# matchbox_bob_v11.net
KiCad netlist of a schematic drawn in EAGLE
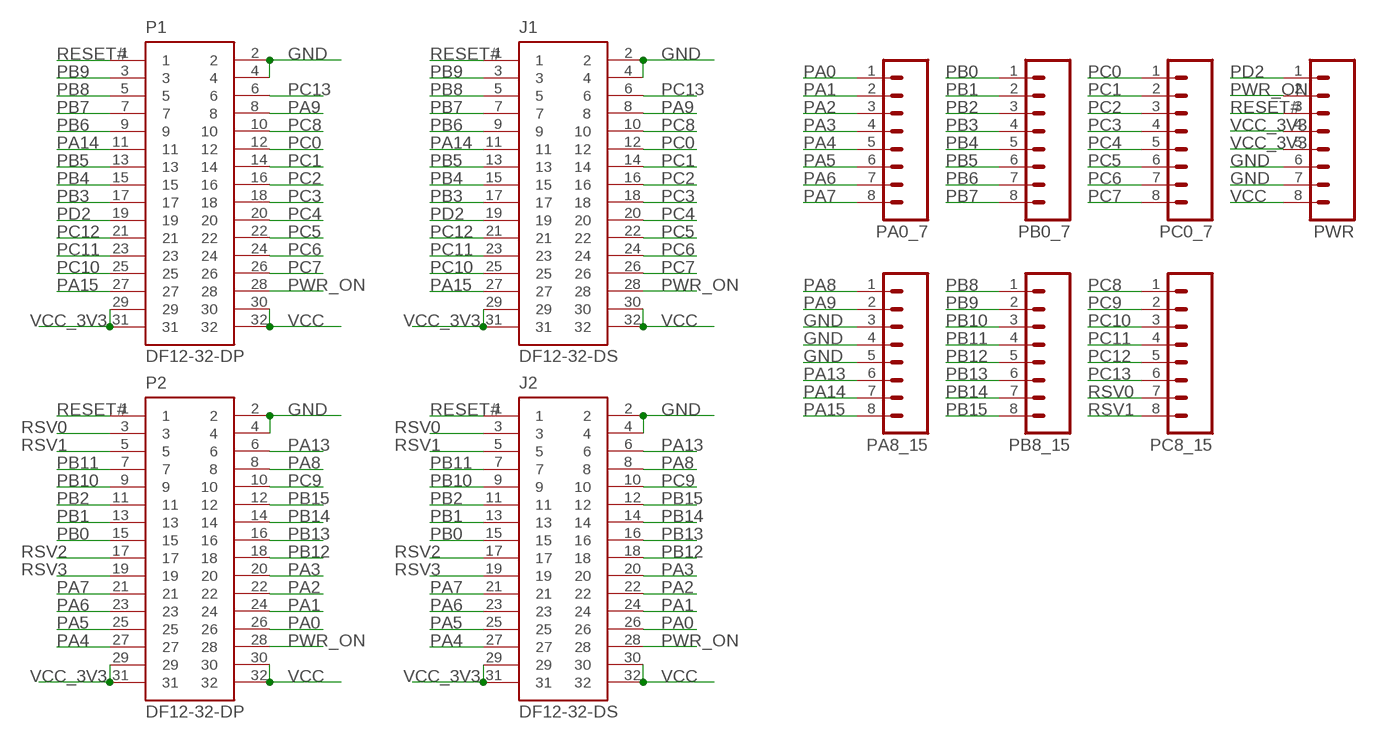
[diagram p0: schematic, sheet 1]

(export (version "E")
  (design (tool "Eeschema 10.0.6"))
  (components
    (comp (ref "J1")
      (value "DF12-32-DS")
      (footprint "eagle-import:DF12-32-DS")
      (fields (field (name "PARTNO") "AS-ITM-00012"))
      (libsource (lib "eagle-import") (part "AS-ITM-00012"))
    )
    (comp (ref "J2")
      (value "DF12-32-DS")
      (footprint "eagle-import:DF12-32-DS")
      (fields (field (name "PARTNO") "AS-ITM-00012"))
      (libsource (lib "eagle-import") (part "AS-ITM-00012"))
    )
    (comp (ref "P1")
      (value "DF12-32-DP")
      (footprint "eagle-import:DF12-32-DP")
      (fields (field (name "PARTNO") "AS-ITM-00015"))
      (libsource (lib "eagle-import") (part "AS-ITM-00015"))
    )
    (comp (ref "P2")
      (value "DF12-32-DP")
      (footprint "eagle-import:DF12-32-DP")
      (fields (field (name "PARTNO") "AS-ITM-00015"))
      (libsource (lib "eagle-import") (part "AS-ITM-00015"))
    )
    (comp (ref "PA0_7")
      (value "M08FEMALE_LOCK")
      (footprint "eagle-import:1X08_FEMALE_LOCK")
      (libsource (lib "eagle-import") (part "M08FEMALE_LOCK"))
    )
    (comp (ref "PA8_15")
      (value "M08FEMALE_LOCK")
      (footprint "eagle-import:1X08_FEMALE_LOCK")
      (libsource (lib "eagle-import") (part "M08FEMALE_LOCK"))
    )
    (comp (ref "PB0_7")
      (value "M08FEMALE_LOCK")
      (footprint "eagle-import:1X08_FEMALE_LOCK")
      (libsource (lib "eagle-import") (part "M08FEMALE_LOCK"))
    )
    (comp (ref "PB8_15")
      (value "M08FEMALE_LOCK")
      (footprint "eagle-import:1X08_FEMALE_LOCK")
      (libsource (lib "eagle-import") (part "M08FEMALE_LOCK"))
    )
    (comp (ref "PC0_7")
      (value "M08FEMALE_LOCK")
      (footprint "eagle-import:1X08_FEMALE_LOCK")
      (libsource (lib "eagle-import") (part "M08FEMALE_LOCK"))
    )
    (comp (ref "PC8_15")
      (value "M08FEMALE_LOCK")
      (footprint "eagle-import:1X08_FEMALE_LOCK")
      (libsource (lib "eagle-import") (part "M08FEMALE_LOCK"))
    )
    (comp (ref "PWR")
      (value "M08FEMALE_LOCK")
      (footprint "eagle-import:1X08_FEMALE_LOCK")
      (libsource (lib "eagle-import") (part "M08FEMALE_LOCK"))
    )
  )
  (nets
    (net (code "1") (name "/GND") (class "Default")
      (node (ref "J1") (pin "2") (pinfunction "2_2") (pintype "bidirectional"))
      (node (ref "J1") (pin "4") (pinfunction "4_4") (pintype "bidirectional"))
      (node (ref "J2") (pin "2") (pinfunction "2_2") (pintype "bidirectional"))
      (node (ref "J2") (pin "4") (pinfunction "4_4") (pintype "bidirectional"))
      (node (ref "P1") (pin "2") (pinfunction "2_2") (pintype "bidirectional"))
      (node (ref "P1") (pin "4") (pinfunction "4_4") (pintype "bidirectional"))
      (node (ref "P2") (pin "2") (pinfunction "2_2") (pintype "bidirectional"))
      (node (ref "P2") (pin "4") (pinfunction "4_4") (pintype "bidirectional"))
      (node (ref "PA8_15") (pin "3") (pinfunction "3_3") (pintype "passive"))
      (node (ref "PA8_15") (pin "4") (pinfunction "4_4") (pintype "passive"))
      (node (ref "PA8_15") (pin "5") (pinfunction "5_5") (pintype "passive"))
      (node (ref "PWR") (pin "6") (pinfunction "6_6") (pintype "passive"))
      (node (ref "PWR") (pin "7") (pinfunction "7_7") (pintype "passive"))
    )
    (net (code "2") (name "/PA0") (class "Default")
      (node (ref "J2") (pin "26") (pinfunction "26_26") (pintype "bidirectional"))
      (node (ref "P2") (pin "26") (pinfunction "26_26") (pintype "bidirectional"))
      (node (ref "PA0_7") (pin "1") (pinfunction "1_1") (pintype "passive"))
    )
    (net (code "3") (name "/PA1") (class "Default")
      (node (ref "J2") (pin "24") (pinfunction "24_24") (pintype "bidirectional"))
      (node (ref "P2") (pin "24") (pinfunction "24_24") (pintype "bidirectional"))
      (node (ref "PA0_7") (pin "2") (pinfunction "2_2") (pintype "passive"))
    )
    (net (code "4") (name "/PA2") (class "Default")
      (node (ref "J2") (pin "22") (pinfunction "22_22") (pintype "bidirectional"))
      (node (ref "P2") (pin "22") (pinfunction "22_22") (pintype "bidirectional"))
      (node (ref "PA0_7") (pin "3") (pinfunction "3_3") (pintype "passive"))
    )
    (net (code "5") (name "/PA3") (class "Default")
      (node (ref "J2") (pin "20") (pinfunction "20_20") (pintype "bidirectional"))
      (node (ref "P2") (pin "20") (pinfunction "20_20") (pintype "bidirectional"))
      (node (ref "PA0_7") (pin "4") (pinfunction "4_4") (pintype "passive"))
    )
    (net (code "6") (name "/PA4") (class "Default")
      (node (ref "J2") (pin "27") (pinfunction "27_27") (pintype "bidirectional"))
      (node (ref "P2") (pin "27") (pinfunction "27_27") (pintype "bidirectional"))
      (node (ref "PA0_7") (pin "5") (pinfunction "5_5") (pintype "passive"))
    )
    (net (code "7") (name "/PA5") (class "Default")
      (node (ref "J2") (pin "25") (pinfunction "25_25") (pintype "bidirectional"))
      (node (ref "P2") (pin "25") (pinfunction "25_25") (pintype "bidirectional"))
      (node (ref "PA0_7") (pin "6") (pinfunction "6_6") (pintype "passive"))
    )
    (net (code "8") (name "/PA6") (class "Default")
      (node (ref "J2") (pin "23") (pinfunction "23_23") (pintype "bidirectional"))
      (node (ref "P2") (pin "23") (pinfunction "23_23") (pintype "bidirectional"))
      (node (ref "PA0_7") (pin "7") (pinfunction "7_7") (pintype "passive"))
    )
    (net (code "9") (name "/PA7") (class "Default")
      (node (ref "J2") (pin "21") (pinfunction "21_21") (pintype "bidirectional"))
      (node (ref "P2") (pin "21") (pinfunction "21_21") (pintype "bidirectional"))
      (node (ref "PA0_7") (pin "8") (pinfunction "8_8") (pintype "passive"))
    )
    (net (code "10") (name "/PA8") (class "Default")
      (node (ref "J2") (pin "8") (pinfunction "8_8") (pintype "bidirectional"))
      (node (ref "P2") (pin "8") (pinfunction "8_8") (pintype "bidirectional"))
      (node (ref "PA8_15") (pin "1") (pinfunction "1_1") (pintype "passive"))
    )
    (net (code "11") (name "/PA9") (class "Default")
      (node (ref "J1") (pin "8") (pinfunction "8_8") (pintype "bidirectional"))
      (node (ref "P1") (pin "8") (pinfunction "8_8") (pintype "bidirectional"))
      (node (ref "PA8_15") (pin "2") (pinfunction "2_2") (pintype "passive"))
    )
    (net (code "12") (name "/PA13") (class "Default")
      (node (ref "J2") (pin "6") (pinfunction "6_6") (pintype "bidirectional"))
      (node (ref "P2") (pin "6") (pinfunction "6_6") (pintype "bidirectional"))
      (node (ref "PA8_15") (pin "6") (pinfunction "6_6") (pintype "passive"))
    )
    (net (code "13") (name "/PA14") (class "Default")
      (node (ref "J1") (pin "11") (pinfunction "11_11") (pintype "bidirectional"))
      (node (ref "P1") (pin "11") (pinfunction "11_11") (pintype "bidirectional"))
      (node (ref "PA8_15") (pin "7") (pinfunction "7_7") (pintype "passive"))
    )
    (net (code "14") (name "/PA15") (class "Default")
      (node (ref "J1") (pin "27") (pinfunction "27_27") (pintype "bidirectional"))
      (node (ref "P1") (pin "27") (pinfunction "27_27") (pintype "bidirectional"))
      (node (ref "PA8_15") (pin "8") (pinfunction "8_8") (pintype "passive"))
    )
    (net (code "15") (name "/PB0") (class "Default")
      (node (ref "J2") (pin "15") (pinfunction "15_15") (pintype "bidirectional"))
      (node (ref "P2") (pin "15") (pinfunction "15_15") (pintype "bidirectional"))
      (node (ref "PB0_7") (pin "1") (pinfunction "1_1") (pintype "passive"))
    )
    (net (code "16") (name "/PB1") (class "Default")
      (node (ref "J2") (pin "13") (pinfunction "13_13") (pintype "bidirectional"))
      (node (ref "P2") (pin "13") (pinfunction "13_13") (pintype "bidirectional"))
      (node (ref "PB0_7") (pin "2") (pinfunction "2_2") (pintype "passive"))
    )
    (net (code "17") (name "/PB2") (class "Default")
      (node (ref "J2") (pin "11") (pinfunction "11_11") (pintype "bidirectional"))
      (node (ref "P2") (pin "11") (pinfunction "11_11") (pintype "bidirectional"))
      (node (ref "PB0_7") (pin "3") (pinfunction "3_3") (pintype "passive"))
    )
    (net (code "18") (name "/PB3") (class "Default")
      (node (ref "J1") (pin "17") (pinfunction "17_17") (pintype "bidirectional"))
      (node (ref "P1") (pin "17") (pinfunction "17_17") (pintype "bidirectional"))
      (node (ref "PB0_7") (pin "4") (pinfunction "4_4") (pintype "passive"))
    )
    (net (code "19") (name "/PB4") (class "Default")
      (node (ref "J1") (pin "15") (pinfunction "15_15") (pintype "bidirectional"))
      (node (ref "P1") (pin "15") (pinfunction "15_15") (pintype "bidirectional"))
      (node (ref "PB0_7") (pin "5") (pinfunction "5_5") (pintype "passive"))
    )
    (net (code "20") (name "/PB5") (class "Default")
      (node (ref "J1") (pin "13") (pinfunction "13_13") (pintype "bidirectional"))
      (node (ref "P1") (pin "13") (pinfunction "13_13") (pintype "bidirectional"))
      (node (ref "PB0_7") (pin "6") (pinfunction "6_6") (pintype "passive"))
    )
    (net (code "21") (name "/PB6") (class "Default")
      (node (ref "J1") (pin "9") (pinfunction "9_9") (pintype "bidirectional"))
      (node (ref "P1") (pin "9") (pinfunction "9_9") (pintype "bidirectional"))
      (node (ref "PB0_7") (pin "7") (pinfunction "7_7") (pintype "passive"))
    )
    (net (code "22") (name "/PB7") (class "Default")
      (node (ref "J1") (pin "7") (pinfunction "7_7") (pintype "bidirectional"))
      (node (ref "P1") (pin "7") (pinfunction "7_7") (pintype "bidirectional"))
      (node (ref "PB0_7") (pin "8") (pinfunction "8_8") (pintype "passive"))
    )
    (net (code "23") (name "/PB8") (class "Default")
      (node (ref "J1") (pin "5") (pinfunction "5_5") (pintype "bidirectional"))
      (node (ref "P1") (pin "5") (pinfunction "5_5") (pintype "bidirectional"))
      (node (ref "PB8_15") (pin "1") (pinfunction "1_1") (pintype "passive"))
    )
    (net (code "24") (name "/PB9") (class "Default")
      (node (ref "J1") (pin "3") (pinfunction "3_3") (pintype "bidirectional"))
      (node (ref "P1") (pin "3") (pinfunction "3_3") (pintype "bidirectional"))
      (node (ref "PB8_15") (pin "2") (pinfunction "2_2") (pintype "passive"))
    )
    (net (code "25") (name "/PB10") (class "Default")
      (node (ref "J2") (pin "9") (pinfunction "9_9") (pintype "bidirectional"))
      (node (ref "P2") (pin "9") (pinfunction "9_9") (pintype "bidirectional"))
      (node (ref "PB8_15") (pin "3") (pinfunction "3_3") (pintype "passive"))
    )
    (net (code "26") (name "/PB11") (class "Default")
      (node (ref "J2") (pin "7") (pinfunction "7_7") (pintype "bidirectional"))
      (node (ref "P2") (pin "7") (pinfunction "7_7") (pintype "bidirectional"))
      (node (ref "PB8_15") (pin "4") (pinfunction "4_4") (pintype "passive"))
    )
    (net (code "27") (name "/PB12") (class "Default")
      (node (ref "J2") (pin "18") (pinfunction "18_18") (pintype "bidirectional"))
      (node (ref "P2") (pin "18") (pinfunction "18_18") (pintype "bidirectional"))
      (node (ref "PB8_15") (pin "5") (pinfunction "5_5") (pintype "passive"))
    )
    (net (code "28") (name "/PB13") (class "Default")
      (node (ref "J2") (pin "16") (pinfunction "16_16") (pintype "bidirectional"))
      (node (ref "P2") (pin "16") (pinfunction "16_16") (pintype "bidirectional"))
      (node (ref "PB8_15") (pin "6") (pinfunction "6_6") (pintype "passive"))
    )
    (net (code "29") (name "/PB14") (class "Default")
      (node (ref "J2") (pin "14") (pinfunction "14_14") (pintype "bidirectional"))
      (node (ref "P2") (pin "14") (pinfunction "14_14") (pintype "bidirectional"))
      (node (ref "PB8_15") (pin "7") (pinfunction "7_7") (pintype "passive"))
    )
    (net (code "30") (name "/PB15") (class "Default")
      (node (ref "J2") (pin "12") (pinfunction "12_12") (pintype "bidirectional"))
      (node (ref "P2") (pin "12") (pinfunction "12_12") (pintype "bidirectional"))
      (node (ref "PB8_15") (pin "8") (pinfunction "8_8") (pintype "passive"))
    )
    (net (code "31") (name "/PC0") (class "Default")
      (node (ref "J1") (pin "12") (pinfunction "12_12") (pintype "bidirectional"))
      (node (ref "P1") (pin "12") (pinfunction "12_12") (pintype "bidirectional"))
      (node (ref "PC0_7") (pin "1") (pinfunction "1_1") (pintype "passive"))
    )
    (net (code "32") (name "/PC1") (class "Default")
      (node (ref "J1") (pin "14") (pinfunction "14_14") (pintype "bidirectional"))
      (node (ref "P1") (pin "14") (pinfunction "14_14") (pintype "bidirectional"))
      (node (ref "PC0_7") (pin "2") (pinfunction "2_2") (pintype "passive"))
    )
    (net (code "33") (name "/PC2") (class "Default")
      (node (ref "J1") (pin "16") (pinfunction "16_16") (pintype "bidirectional"))
      (node (ref "P1") (pin "16") (pinfunction "16_16") (pintype "bidirectional"))
      (node (ref "PC0_7") (pin "3") (pinfunction "3_3") (pintype "passive"))
    )
    (net (code "34") (name "/PC3") (class "Default")
      (node (ref "J1") (pin "18") (pinfunction "18_18") (pintype "bidirectional"))
      (node (ref "P1") (pin "18") (pinfunction "18_18") (pintype "bidirectional"))
      (node (ref "PC0_7") (pin "4") (pinfunction "4_4") (pintype "passive"))
    )
    (net (code "35") (name "/PC4") (class "Default")
      (node (ref "J1") (pin "20") (pinfunction "20_20") (pintype "bidirectional"))
      (node (ref "P1") (pin "20") (pinfunction "20_20") (pintype "bidirectional"))
      (node (ref "PC0_7") (pin "5") (pinfunction "5_5") (pintype "passive"))
    )
    (net (code "36") (name "/PC5") (class "Default")
      (node (ref "J1") (pin "22") (pinfunction "22_22") (pintype "bidirectional"))
      (node (ref "P1") (pin "22") (pinfunction "22_22") (pintype "bidirectional"))
      (node (ref "PC0_7") (pin "6") (pinfunction "6_6") (pintype "passive"))
    )
    (net (code "37") (name "/PC6") (class "Default")
      (node (ref "J1") (pin "24") (pinfunction "24_24") (pintype "bidirectional"))
      (node (ref "P1") (pin "24") (pinfunction "24_24") (pintype "bidirectional"))
      (node (ref "PC0_7") (pin "7") (pinfunction "7_7") (pintype "passive"))
    )
    (net (code "38") (name "/PC7") (class "Default")
      (node (ref "J1") (pin "26") (pinfunction "26_26") (pintype "bidirectional"))
      (node (ref "P1") (pin "26") (pinfunction "26_26") (pintype "bidirectional"))
      (node (ref "PC0_7") (pin "8") (pinfunction "8_8") (pintype "passive"))
    )
    (net (code "39") (name "/PC8") (class "Default")
      (node (ref "J1") (pin "10") (pinfunction "10_10") (pintype "bidirectional"))
      (node (ref "P1") (pin "10") (pinfunction "10_10") (pintype "bidirectional"))
      (node (ref "PC8_15") (pin "1") (pinfunction "1_1") (pintype "passive"))
    )
    (net (code "40") (name "/PC9") (class "Default")
      (node (ref "J2") (pin "10") (pinfunction "10_10") (pintype "bidirectional"))
      (node (ref "P2") (pin "10") (pinfunction "10_10") (pintype "bidirectional"))
      (node (ref "PC8_15") (pin "2") (pinfunction "2_2") (pintype "passive"))
    )
    (net (code "41") (name "/PC10") (class "Default")
      (node (ref "J1") (pin "25") (pinfunction "25_25") (pintype "bidirectional"))
      (node (ref "P1") (pin "25") (pinfunction "25_25") (pintype "bidirectional"))
      (node (ref "PC8_15") (pin "3") (pinfunction "3_3") (pintype "passive"))
    )
    (net (code "42") (name "/PC11") (class "Default")
      (node (ref "J1") (pin "23") (pinfunction "23_23") (pintype "bidirectional"))
      (node (ref "P1") (pin "23") (pinfunction "23_23") (pintype "bidirectional"))
      (node (ref "PC8_15") (pin "4") (pinfunction "4_4") (pintype "passive"))
    )
    (net (code "43") (name "/PC12") (class "Default")
      (node (ref "J1") (pin "21") (pinfunction "21_21") (pintype "bidirectional"))
      (node (ref "P1") (pin "21") (pinfunction "21_21") (pintype "bidirectional"))
      (node (ref "PC8_15") (pin "5") (pinfunction "5_5") (pintype "passive"))
    )
    (net (code "44") (name "/PC13") (class "Default")
      (node (ref "J1") (pin "6") (pinfunction "6_6") (pintype "bidirectional"))
      (node (ref "P1") (pin "6") (pinfunction "6_6") (pintype "bidirectional"))
      (node (ref "PC8_15") (pin "6") (pinfunction "6_6") (pintype "passive"))
    )
    (net (code "45") (name "/PD2") (class "Default")
      (node (ref "J1") (pin "19") (pinfunction "19_19") (pintype "bidirectional"))
      (node (ref "P1") (pin "19") (pinfunction "19_19") (pintype "bidirectional"))
      (node (ref "PWR") (pin "1") (pinfunction "1_1") (pintype "passive"))
    )
    (net (code "46") (name "/PWR_ON") (class "Default")
      (node (ref "J1") (pin "28") (pinfunction "28_28") (pintype "bidirectional"))
      (node (ref "J2") (pin "28") (pinfunction "28_28") (pintype "bidirectional"))
      (node (ref "P1") (pin "28") (pinfunction "28_28") (pintype "bidirectional"))
      (node (ref "P2") (pin "28") (pinfunction "28_28") (pintype "bidirectional"))
      (node (ref "PWR") (pin "2") (pinfunction "2_2") (pintype "passive"))
    )
    (net (code "47") (name "/RESET#") (class "Default")
      (node (ref "J1") (pin "1") (pinfunction "1_1") (pintype "bidirectional"))
      (node (ref "J2") (pin "1") (pinfunction "1_1") (pintype "bidirectional"))
      (node (ref "P1") (pin "1") (pinfunction "1_1") (pintype "bidirectional"))
      (node (ref "P2") (pin "1") (pinfunction "1_1") (pintype "bidirectional"))
      (node (ref "PWR") (pin "3") (pinfunction "3_3") (pintype "passive"))
    )
    (net (code "48") (name "/RSV0") (class "Default")
      (node (ref "J2") (pin "3") (pinfunction "3_3") (pintype "bidirectional"))
      (node (ref "P2") (pin "3") (pinfunction "3_3") (pintype "bidirectional"))
      (node (ref "PC8_15") (pin "7") (pinfunction "7_7") (pintype "passive"))
    )
    (net (code "49") (name "/RSV1") (class "Default")
      (node (ref "J2") (pin "5") (pinfunction "5_5") (pintype "bidirectional"))
      (node (ref "P2") (pin "5") (pinfunction "5_5") (pintype "bidirectional"))
      (node (ref "PC8_15") (pin "8") (pinfunction "8_8") (pintype "passive"))
    )
    (net (code "50") (name "/RSV2") (class "Default")
      (node (ref "J2") (pin "17") (pinfunction "17_17") (pintype "bidirectional"))
      (node (ref "P2") (pin "17") (pinfunction "17_17") (pintype "bidirectional"))
    )
    (net (code "51") (name "/RSV3") (class "Default")
      (node (ref "J2") (pin "19") (pinfunction "19_19") (pintype "bidirectional"))
      (node (ref "P2") (pin "19") (pinfunction "19_19") (pintype "bidirectional"))
    )
    (net (code "52") (name "/VCC") (class "Default")
      (node (ref "J1") (pin "30") (pinfunction "30_30") (pintype "bidirectional"))
      (node (ref "J1") (pin "32") (pinfunction "32_32") (pintype "bidirectional"))
      (node (ref "J2") (pin "30") (pinfunction "30_30") (pintype "bidirectional"))
      (node (ref "J2") (pin "32") (pinfunction "32_32") (pintype "bidirectional"))
      (node (ref "P1") (pin "30") (pinfunction "30_30") (pintype "bidirectional"))
      (node (ref "P1") (pin "32") (pinfunction "32_32") (pintype "bidirectional"))
      (node (ref "P2") (pin "30") (pinfunction "30_30") (pintype "bidirectional"))
      (node (ref "P2") (pin "32") (pinfunction "32_32") (pintype "bidirectional"))
      (node (ref "PWR") (pin "8") (pinfunction "8_8") (pintype "passive"))
    )
    (net (code "53") (name "/VCC_3V3") (class "Default")
      (node (ref "J1") (pin "29") (pinfunction "29_29") (pintype "bidirectional"))
      (node (ref "J1") (pin "31") (pinfunction "31_31") (pintype "bidirectional"))
      (node (ref "J2") (pin "29") (pinfunction "29_29") (pintype "bidirectional"))
      (node (ref "J2") (pin "31") (pinfunction "31_31") (pintype "bidirectional"))
      (node (ref "P1") (pin "29") (pinfunction "29_29") (pintype "bidirectional"))
      (node (ref "P1") (pin "31") (pinfunction "31_31") (pintype "bidirectional"))
      (node (ref "P2") (pin "29") (pinfunction "29_29") (pintype "bidirectional"))
      (node (ref "P2") (pin "31") (pinfunction "31_31") (pintype "bidirectional"))
      (node (ref "PWR") (pin "4") (pinfunction "4_4") (pintype "passive"))
      (node (ref "PWR") (pin "5") (pinfunction "5_5") (pintype "passive"))
    )
  )
)
